# DMX.net
KiCad netlist of a schematic drawn in EAGLE
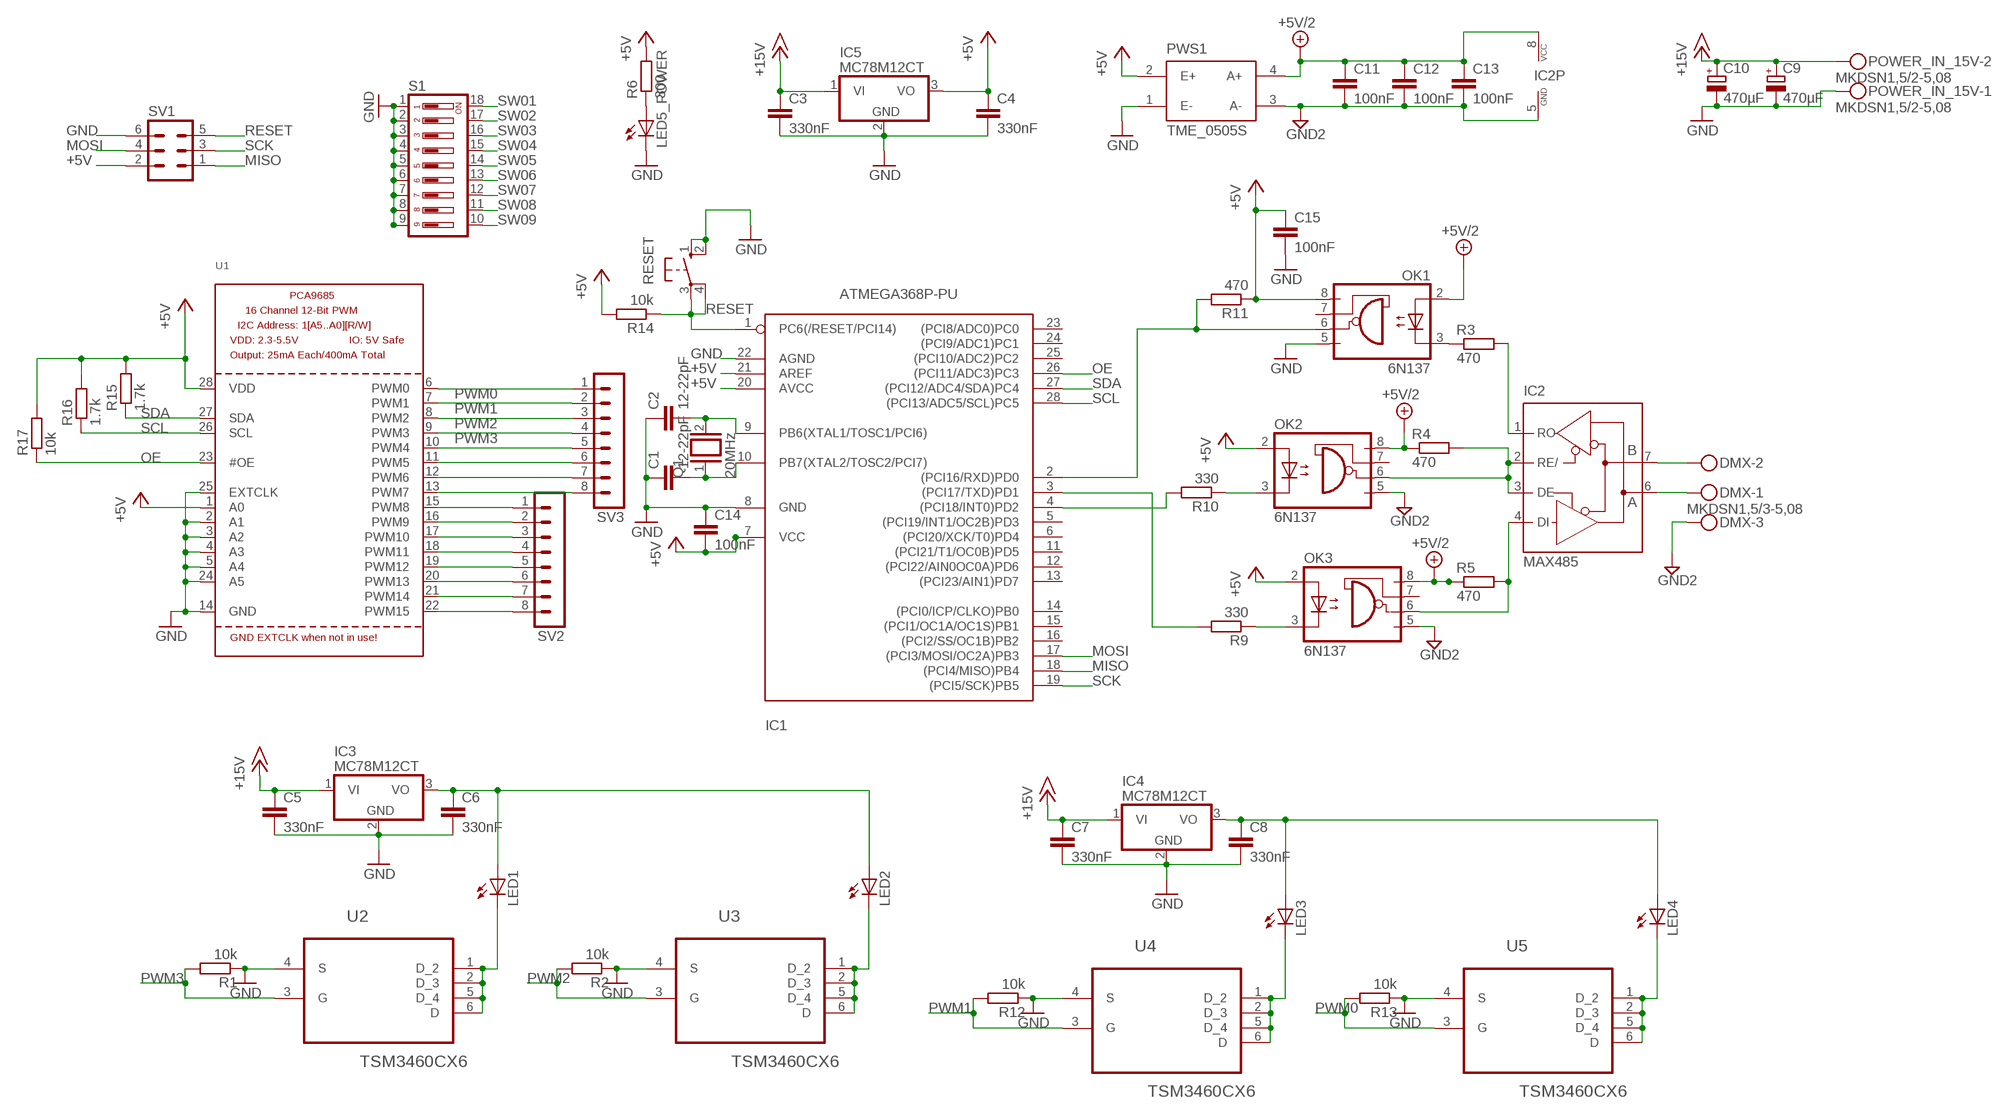
[diagram p0: schematic, sheet 1]

(export (version "E")
  (design (tool "Eeschema 10.0.6"))
  (components
    (comp (ref "C1")
      (value "12-22pF")
      (footprint "eagle-import:C025-025X050")
      (libsource (lib "eagle-import") (part "C-EU025-025X050"))
    )
    (comp (ref "C2")
      (value "12-22pF")
      (footprint "eagle-import:C025-025X050")
      (libsource (lib "eagle-import") (part "C-EU025-025X050"))
    )
    (comp (ref "C3")
      (value "330nF")
      (footprint "eagle-import:C050-025X075")
      (libsource (lib "eagle-import") (part "C-EU050-025X075"))
    )
    (comp (ref "C4")
      (value "330nF")
      (footprint "eagle-import:C050-025X075")
      (libsource (lib "eagle-import") (part "C-EU050-025X075"))
    )
    (comp (ref "C5")
      (value "330nF")
      (footprint "eagle-import:C050-025X075")
      (libsource (lib "eagle-import") (part "C-EU050-025X075"))
    )
    (comp (ref "C6")
      (value "330nF")
      (footprint "eagle-import:C050-025X075")
      (libsource (lib "eagle-import") (part "C-EU050-025X075"))
    )
    (comp (ref "C7")
      (value "330nF")
      (footprint "eagle-import:C050-025X075")
      (libsource (lib "eagle-import") (part "C-EU050-025X075"))
    )
    (comp (ref "C8")
      (value "330nF")
      (footprint "eagle-import:C050-025X075")
      (libsource (lib "eagle-import") (part "C-EU050-025X075"))
    )
    (comp (ref "C9")
      (value "470µF")
      (footprint "eagle-import:E5-10,5")
      (libsource (lib "eagle-import") (part "CPOL-EUE5-10.5"))
    )
    (comp (ref "C10")
      (value "470µF")
      (footprint "eagle-import:E5-10,5")
      (libsource (lib "eagle-import") (part "CPOL-EUE5-10.5"))
    )
    (comp (ref "C11")
      (value "100nF")
      (footprint "eagle-import:C050-025X075")
      (libsource (lib "eagle-import") (part "C-EU050-025X075"))
    )
    (comp (ref "C12")
      (value "100nF")
      (footprint "eagle-import:C050-025X075")
      (libsource (lib "eagle-import") (part "C-EU050-025X075"))
    )
    (comp (ref "C13")
      (value "100nF")
      (footprint "eagle-import:C050-025X075")
      (libsource (lib "eagle-import") (part "C-EU050-025X075"))
    )
    (comp (ref "C14")
      (value "100nF")
      (footprint "eagle-import:C050-025X075")
      (libsource (lib "eagle-import") (part "C-EU050-025X075"))
    )
    (comp (ref "C15")
      (value "100nF")
      (footprint "eagle-import:C050-025X075")
      (libsource (lib "eagle-import") (part "C-EU050-025X075"))
    )
    (comp (ref "DMX")
      (value "MKDSN1,5/3-5,08")
      (footprint "eagle-import:MKDSN1,5_3-5,08")
      (fields (field (name "MPN") "SMKDSN1,5/3-5,08"))
      (libsource (lib "eagle-import") (part "MKDSN1,5/3-5,08"))
    )
    (comp (ref "IC1")
      (value "ATMEGA368P-PU")
      (footprint "eagle-import:DIL28-3")
      (libsource (lib "eagle-import") (part "ATMEGA168P-20"))
    )
    (comp (ref "IC2")
      (value "MAX485")
      (footprint "eagle-import:DIL08")
      (fields (field (name "MPN") "MAX481CPA+") (field (name "MPN_1") "MAX485"))
      (libsource (lib "eagle-import") (part "MAX481CPA"))
    )
    (comp (ref "IC3")
      (value "MC78M12CT")
      (footprint "eagle-import:TO220V")
      (libsource (lib "eagle-import") (part "MC78MT12C"))
    )
    (comp (ref "IC4")
      (value "MC78M12CT")
      (footprint "eagle-import:TO220V")
      (libsource (lib "eagle-import") (part "MC78MT12C"))
    )
    (comp (ref "IC5")
      (value "MC78M12CT")
      (footprint "eagle-import:TO220V")
      (libsource (lib "eagle-import") (part "MC78MT12C"))
    )
    (comp (ref "LED1")
      (value "LED5MM")
      (footprint "eagle-import:LED5MM")
      (libsource (lib "eagle-import") (part "LED5MM"))
    )
    (comp (ref "LED2")
      (value "LED5MM")
      (footprint "eagle-import:LED5MM")
      (libsource (lib "eagle-import") (part "LED5MM"))
    )
    (comp (ref "LED3")
      (value "LED5MM")
      (footprint "eagle-import:LED5MM")
      (libsource (lib "eagle-import") (part "LED5MM"))
    )
    (comp (ref "LED4")
      (value "LED5MM")
      (footprint "eagle-import:LED5MM")
      (libsource (lib "eagle-import") (part "LED5MM"))
    )
    (comp (ref "LED5_POWER")
      (value "LED5MM")
      (footprint "eagle-import:LED5MM")
      (libsource (lib "eagle-import") (part "LED5MM"))
    )
    (comp (ref "OK1")
      (value "6N137")
      (footprint "eagle-import:DIL08")
      (libsource (lib "eagle-import") (part "6N137"))
    )
    (comp (ref "OK2")
      (value "6N137")
      (footprint "eagle-import:DIL08")
      (libsource (lib "eagle-import") (part "6N137"))
    )
    (comp (ref "OK3")
      (value "6N137")
      (footprint "eagle-import:DIL08")
      (libsource (lib "eagle-import") (part "6N137"))
    )
    (comp (ref "POWER_IN_15V")
      (value "MKDSN1,5/2-5,08")
      (footprint "eagle-import:MKDSN1,5_2-5,08")
      (fields (field (name "MPN") "MKDSN 1,5/2-5.08"))
      (libsource (lib "eagle-import") (part "MKDSN1,5/2-5,08"))
    )
    (comp (ref "PWS1")
      (value "TME_0505S")
      (footprint "eagle-import:TMEXXXXS")
      (fields (field (name "MPN") "TME 0505S"))
      (libsource (lib "eagle-import") (part "TME_S0505"))
    )
    (comp (ref "Q1")
      (value "20MHz")
      (footprint "eagle-import:QS")
      (libsource (lib "eagle-import") (part "XTAL/S"))
    )
    (comp (ref "R1")
      (value "10k")
      (footprint "eagle-import:0207_7")
      (libsource (lib "eagle-import") (part "R-EU_0207/7"))
    )
    (comp (ref "R2")
      (value "10k")
      (footprint "eagle-import:0207_7")
      (libsource (lib "eagle-import") (part "R-EU_0207/7"))
    )
    (comp (ref "R3")
      (value "470")
      (footprint "eagle-import:0207_7")
      (libsource (lib "eagle-import") (part "R-EU_0207/7"))
    )
    (comp (ref "R4")
      (value "470")
      (footprint "eagle-import:0207_7")
      (libsource (lib "eagle-import") (part "R-EU_0207/7"))
    )
    (comp (ref "R5")
      (value "470")
      (footprint "eagle-import:0207_7")
      (libsource (lib "eagle-import") (part "R-EU_0207/7"))
    )
    (comp (ref "R6")
      (value "300")
      (footprint "eagle-import:0204_7")
      (libsource (lib "eagle-import") (part "R-EU_0204/7"))
    )
    (comp (ref "R9")
      (value "330")
      (footprint "eagle-import:0207_7")
      (libsource (lib "eagle-import") (part "R-EU_0207/7"))
    )
    (comp (ref "R10")
      (value "330")
      (footprint "eagle-import:0207_7")
      (libsource (lib "eagle-import") (part "R-EU_0207/7"))
    )
    (comp (ref "R11")
      (value "470")
      (footprint "eagle-import:0207_7")
      (libsource (lib "eagle-import") (part "R-EU_0207/7"))
    )
    (comp (ref "R12")
      (value "10k")
      (footprint "eagle-import:0207_7")
      (libsource (lib "eagle-import") (part "R-EU_0207/7"))
    )
    (comp (ref "R13")
      (value "10k")
      (footprint "eagle-import:0207_7")
      (libsource (lib "eagle-import") (part "R-EU_0207/7"))
    )
    (comp (ref "R14")
      (value "10k")
      (footprint "eagle-import:0204_7")
      (libsource (lib "eagle-import") (part "R-EU_0204/7"))
    )
    (comp (ref "R15")
      (value "1.7k")
      (footprint "eagle-import:0204_7")
      (libsource (lib "eagle-import") (part "R-EU_0204/7"))
    )
    (comp (ref "R16")
      (value "1.7k")
      (footprint "eagle-import:0204_7")
      (libsource (lib "eagle-import") (part "R-EU_0204/7"))
    )
    (comp (ref "R17")
      (value "10k")
      (footprint "eagle-import:0204_7")
      (libsource (lib "eagle-import") (part "R-EU_0204/7"))
    )
    (comp (ref "RESET")
      (value "10-XX")
      (footprint "eagle-import:B3F-10XX")
      (fields (field (name "MPN") "B3F-1000"))
      (libsource (lib "eagle-import") (part "10-XX"))
    )
    (comp (ref "S1")
      (value "DP09")
      (footprint "eagle-import:DP-09")
      (fields (field (name "MPN") "MCDP09"))
      (libsource (lib "eagle-import") (part "DP09"))
    )
    (comp (ref "SV1")
      (value "MA03-2")
      (footprint "eagle-import:MA03-2")
      (libsource (lib "eagle-import") (part "MA03-2"))
    )
    (comp (ref "SV2")
      (value "MA08-1")
      (footprint "eagle-import:MA08-1")
      (libsource (lib "eagle-import") (part "MA08-1"))
    )
    (comp (ref "SV3")
      (value "MA08-1")
      (footprint "eagle-import:MA08-1")
      (libsource (lib "eagle-import") (part "MA08-1"))
    )
    (comp (ref "U1")
      (value "PCA9685")
      (footprint "eagle-import:TSSOP28")
      (libsource (lib "eagle-import") (part "PCA9685"))
    )
    (comp (ref "U2")
      (value "TSM3460CX6")
      (footprint "eagle-import:SOT95P280X120-6N")
      (libsource (lib "eagle-import") (part "TSM3460CX6"))
    )
    (comp (ref "U3")
      (value "TSM3460CX6")
      (footprint "eagle-import:SOT95P280X120-6N")
      (libsource (lib "eagle-import") (part "TSM3460CX6"))
    )
    (comp (ref "U4")
      (value "TSM3460CX6")
      (footprint "eagle-import:SOT95P280X120-6N")
      (libsource (lib "eagle-import") (part "TSM3460CX6"))
    )
    (comp (ref "U5")
      (value "TSM3460CX6")
      (footprint "eagle-import:SOT95P280X120-6N")
      (libsource (lib "eagle-import") (part "TSM3460CX6"))
    )
  )
  (nets
    (net (code "1") (name "+5V") (class "Default")
      (node (ref "C14") (pin "2") (pinfunction "2_2") (pintype "passive"))
      (node (ref "C15") (pin "1") (pinfunction "1_1") (pintype "passive"))
      (node (ref "C4") (pin "1") (pinfunction "1_1") (pintype "passive"))
      (node (ref "IC1") (pin "20") (pinfunction "AVCC_20") (pintype "bidirectional"))
      (node (ref "IC1") (pin "21") (pinfunction "AREF_21") (pintype "bidirectional"))
      (node (ref "IC1") (pin "7") (pinfunction "VCC_7") (pintype "bidirectional"))
      (node (ref "IC5") (pin "3") (pinfunction "VO_3") (pintype "passive"))
      (node (ref "OK1") (pin "8") (pinfunction "VCC_8") (pintype "passive"))
      (node (ref "OK2") (pin "2") (pinfunction "A_2") (pintype "passive"))
      (node (ref "OK3") (pin "2") (pinfunction "A_2") (pintype "passive"))
      (node (ref "PWS1") (pin "2") (pinfunction "E+_2") (pintype "input"))
      (node (ref "R11") (pin "1") (pinfunction "1_1") (pintype "passive"))
      (node (ref "R14") (pin "2") (pinfunction "2_2") (pintype "passive"))
      (node (ref "R15") (pin "2") (pinfunction "2_2") (pintype "passive"))
      (node (ref "R16") (pin "2") (pinfunction "2_2") (pintype "passive"))
      (node (ref "R17") (pin "2") (pinfunction "2_2") (pintype "passive"))
      (node (ref "R6") (pin "2") (pinfunction "2_2") (pintype "passive"))
      (node (ref "SV1") (pin "2") (pinfunction "2_2") (pintype "passive"))
      (node (ref "U1") (pin "1") (pinfunction "A0_1") (pintype "bidirectional"))
      (node (ref "U1") (pin "28") (pinfunction "VDD_28") (pintype "power_in"))
    )
    (net (code "2") (name "+5V{slash}2") (class "Default")
      (node (ref "C11") (pin "1") (pinfunction "1_1") (pintype "passive"))
      (node (ref "C12") (pin "1") (pinfunction "1_1") (pintype "passive"))
      (node (ref "C13") (pin "1") (pinfunction "1_1") (pintype "passive"))
      (node (ref "IC2") (pin "8") (pinfunction "VCC_8") (pintype "power_in"))
      (node (ref "OK1") (pin "2") (pinfunction "A_2") (pintype "passive"))
      (node (ref "OK2") (pin "8") (pinfunction "VCC_8") (pintype "passive"))
      (node (ref "OK3") (pin "8") (pinfunction "VCC_8") (pintype "passive"))
      (node (ref "PWS1") (pin "4") (pinfunction "A+_4") (pintype "output"))
      (node (ref "R4") (pin "1") (pinfunction "1_1") (pintype "passive"))
      (node (ref "R5") (pin "1") (pinfunction "1_1") (pintype "passive"))
    )
    (net (code "3") (name "+15V") (class "Default")
      (node (ref "C10") (pin "+") (pinfunction "+_+") (pintype "passive"))
      (node (ref "C3") (pin "1") (pinfunction "1_1") (pintype "passive"))
      (node (ref "C5") (pin "1") (pinfunction "1_1") (pintype "passive"))
      (node (ref "C7") (pin "1") (pinfunction "1_1") (pintype "passive"))
      (node (ref "C9") (pin "+") (pinfunction "+_+") (pintype "passive"))
      (node (ref "IC3") (pin "1") (pinfunction "VI_1") (pintype "input"))
      (node (ref "IC4") (pin "1") (pinfunction "VI_1") (pintype "input"))
      (node (ref "IC5") (pin "1") (pinfunction "VI_1") (pintype "input"))
      (node (ref "POWER_IN_15V") (pin "2") (pinfunction "KL_2") (pintype "passive"))
    )
    (net (code "4") (name "/MISO") (class "Default")
      (node (ref "IC1") (pin "18") (pinfunction "(PCI4/MISO)PB4_18") (pintype "bidirectional"))
      (node (ref "SV1") (pin "1") (pinfunction "1_1") (pintype "passive"))
    )
    (net (code "5") (name "/MOSI") (class "Default")
      (node (ref "IC1") (pin "17") (pinfunction "(PCI3/MOSI/OC2A)PB3_17") (pintype "bidirectional"))
      (node (ref "SV1") (pin "4") (pinfunction "4_4") (pintype "passive"))
    )
    (net (code "6") (name "/OE") (class "Default")
      (node (ref "IC1") (pin "26") (pinfunction "(PCI11/ADC3)PC3_26") (pintype "bidirectional"))
      (node (ref "R17") (pin "1") (pinfunction "1_1") (pintype "passive"))
      (node (ref "U1") (pin "23") (pinfunction "#OE_23") (pintype "input"))
    )
    (net (code "7") (name "/PWM0") (class "Default")
      (node (ref "R13") (pin "2") (pinfunction "2_2") (pintype "passive"))
      (node (ref "SV3") (pin "1") (pinfunction "1_1") (pintype "passive"))
      (node (ref "U1") (pin "6") (pinfunction "PWM0_6") (pintype "output"))
      (node (ref "U5") (pin "3") (pinfunction "G_3") (pintype "passive"))
    )
    (net (code "8") (name "/PWM1") (class "Default")
      (node (ref "R12") (pin "2") (pinfunction "2_2") (pintype "passive"))
      (node (ref "SV3") (pin "2") (pinfunction "2_2") (pintype "passive"))
      (node (ref "U1") (pin "7") (pinfunction "PWM1_7") (pintype "output"))
      (node (ref "U4") (pin "3") (pinfunction "G_3") (pintype "passive"))
    )
    (net (code "9") (name "/PWM2") (class "Default")
      (node (ref "R2") (pin "2") (pinfunction "2_2") (pintype "passive"))
      (node (ref "SV3") (pin "3") (pinfunction "3_3") (pintype "passive"))
      (node (ref "U1") (pin "8") (pinfunction "PWM2_8") (pintype "output"))
      (node (ref "U3") (pin "3") (pinfunction "G_3") (pintype "passive"))
    )
    (net (code "10") (name "/PWM3") (class "Default")
      (node (ref "R1") (pin "2") (pinfunction "2_2") (pintype "passive"))
      (node (ref "SV3") (pin "4") (pinfunction "4_4") (pintype "passive"))
      (node (ref "U1") (pin "9") (pinfunction "PWM3_9") (pintype "output"))
      (node (ref "U2") (pin "3") (pinfunction "G_3") (pintype "passive"))
    )
    (net (code "11") (name "/RESET") (class "Default")
      (node (ref "IC1") (pin "1") (pinfunction "PC6(/RESET/PCI14)_1") (pintype "bidirectional"))
      (node (ref "R14") (pin "1") (pinfunction "1_1") (pintype "passive"))
      (node (ref "RESET") (pin "3") (pinfunction "P_3") (pintype "passive"))
      (node (ref "RESET") (pin "4") (pinfunction "P1_4") (pintype "passive"))
      (node (ref "SV1") (pin "5") (pinfunction "5_5") (pintype "passive"))
    )
    (net (code "12") (name "/SCK") (class "Default")
      (node (ref "IC1") (pin "19") (pinfunction "(PCI5/SCK)PB5_19") (pintype "bidirectional"))
      (node (ref "SV1") (pin "3") (pinfunction "3_3") (pintype "passive"))
    )
    (net (code "13") (name "/SCL") (class "Default")
      (node (ref "IC1") (pin "28") (pinfunction "(PCI13/ADC5/SCL)PC5_28") (pintype "bidirectional"))
      (node (ref "R16") (pin "1") (pinfunction "1_1") (pintype "passive"))
      (node (ref "U1") (pin "26") (pinfunction "SCL_26") (pintype "bidirectional"))
    )
    (net (code "14") (name "/SDA") (class "Default")
      (node (ref "IC1") (pin "27") (pinfunction "(PCI12/ADC4/SDA)PC4_27") (pintype "bidirectional"))
      (node (ref "R15") (pin "1") (pinfunction "1_1") (pintype "passive"))
      (node (ref "U1") (pin "27") (pinfunction "SDA_27") (pintype "bidirectional"))
    )
    (net (code "15") (name "/SW01") (class "Default")
      (node (ref "S1") (pin "18") (pinfunction "18_18") (pintype "passive"))
    )
    (net (code "16") (name "/SW02") (class "Default")
      (node (ref "S1") (pin "17") (pinfunction "17_17") (pintype "passive"))
    )
    (net (code "17") (name "/SW03") (class "Default")
      (node (ref "S1") (pin "16") (pinfunction "16_16") (pintype "passive"))
    )
    (net (code "18") (name "/SW04") (class "Default")
      (node (ref "S1") (pin "15") (pinfunction "15_15") (pintype "passive"))
    )
    (net (code "19") (name "/SW05") (class "Default")
      (node (ref "S1") (pin "14") (pinfunction "14_14") (pintype "passive"))
    )
    (net (code "20") (name "/SW06") (class "Default")
      (node (ref "S1") (pin "13") (pinfunction "13_13") (pintype "passive"))
    )
    (net (code "21") (name "/SW07") (class "Default")
      (node (ref "S1") (pin "12") (pinfunction "12_12") (pintype "passive"))
    )
    (net (code "22") (name "/SW08") (class "Default")
      (node (ref "S1") (pin "11") (pinfunction "11_11") (pintype "passive"))
    )
    (net (code "23") (name "/SW09") (class "Default")
      (node (ref "S1") (pin "10") (pinfunction "10_10") (pintype "passive"))
    )
    (net (code "24") (name "GND") (class "Default")
      (node (ref "C1") (pin "1") (pinfunction "1_1") (pintype "passive"))
      (node (ref "C10") (pin "-") (pinfunction "-_-") (pintype "passive"))
      (node (ref "C14") (pin "1") (pinfunction "1_1") (pintype "passive"))
      (node (ref "C15") (pin "2") (pinfunction "2_2") (pintype "passive"))
      (node (ref "C2") (pin "1") (pinfunction "1_1") (pintype "passive"))
      (node (ref "C3") (pin "2") (pinfunction "2_2") (pintype "passive"))
      (node (ref "C4") (pin "2") (pinfunction "2_2") (pintype "passive"))
      (node (ref "C5") (pin "2") (pinfunction "2_2") (pintype "passive"))
      (node (ref "C6") (pin "2") (pinfunction "2_2") (pintype "passive"))
      (node (ref "C7") (pin "2") (pinfunction "2_2") (pintype "passive"))
      (node (ref "C8") (pin "2") (pinfunction "2_2") (pintype "passive"))
      (node (ref "C9") (pin "-") (pinfunction "-_-") (pintype "passive"))
      (node (ref "IC1") (pin "22") (pinfunction "AGND_22") (pintype "bidirectional"))
      (node (ref "IC1") (pin "8") (pinfunction "GND_8") (pintype "bidirectional"))
      (node (ref "IC3") (pin "2") (pinfunction "GND_2") (pintype "passive"))
      (node (ref "IC4") (pin "2") (pinfunction "GND_2") (pintype "passive"))
      (node (ref "IC5") (pin "2") (pinfunction "GND_2") (pintype "passive"))
      (node (ref "LED5_POWER") (pin "K") (pinfunction "C_K") (pintype "passive"))
      (node (ref "OK1") (pin "5") (pinfunction "GND_5") (pintype "passive"))
      (node (ref "POWER_IN_15V") (pin "1") (pinfunction "KL_1") (pintype "passive"))
      (node (ref "PWS1") (pin "1") (pinfunction "E-_1") (pintype "input"))
      (node (ref "R1") (pin "1") (pinfunction "1_1") (pintype "passive"))
      (node (ref "R12") (pin "1") (pinfunction "1_1") (pintype "passive"))
      (node (ref "R13") (pin "1") (pinfunction "1_1") (pintype "passive"))
      (node (ref "R2") (pin "1") (pinfunction "1_1") (pintype "passive"))
      (node (ref "RESET") (pin "1") (pinfunction "S_1") (pintype "passive"))
      (node (ref "RESET") (pin "2") (pinfunction "S1_2") (pintype "passive"))
      (node (ref "S1") (pin "1") (pinfunction "1_1") (pintype "passive"))
      (node (ref "S1") (pin "2") (pinfunction "2_2") (pintype "passive"))
      (node (ref "S1") (pin "3") (pinfunction "3_3") (pintype "passive"))
      (node (ref "S1") (pin "4") (pinfunction "4_4") (pintype "passive"))
      (node (ref "S1") (pin "5") (pinfunction "5_5") (pintype "passive"))
      (node (ref "S1") (pin "6") (pinfunction "6_6") (pintype "passive"))
      (node (ref "S1") (pin "7") (pinfunction "7_7") (pintype "passive"))
      (node (ref "S1") (pin "8") (pinfunction "8_8") (pintype "passive"))
      (node (ref "S1") (pin "9") (pinfunction "9_9") (pintype "passive"))
      (node (ref "SV1") (pin "6") (pinfunction "6_6") (pintype "passive"))
      (node (ref "U1") (pin "14") (pinfunction "GND_14") (pintype "power_in"))
      (node (ref "U1") (pin "2") (pinfunction "A1_2") (pintype "bidirectional"))
      (node (ref "U1") (pin "24") (pinfunction "A5_24") (pintype "bidirectional"))
      (node (ref "U1") (pin "25") (pinfunction "EXTCLK_25") (pintype "input"))
      (node (ref "U1") (pin "3") (pinfunction "A2_3") (pintype "bidirectional"))
      (node (ref "U1") (pin "4") (pinfunction "A3_4") (pintype "bidirectional"))
      (node (ref "U1") (pin "5") (pinfunction "A4_5") (pintype "bidirectional"))
      (node (ref "U2") (pin "4") (pinfunction "S_4") (pintype "passive"))
      (node (ref "U3") (pin "4") (pinfunction "S_4") (pintype "passive"))
      (node (ref "U4") (pin "4") (pinfunction "S_4") (pintype "passive"))
      (node (ref "U5") (pin "4") (pinfunction "S_4") (pintype "passive"))
    )
    (net (code "25") (name "GND2") (class "Default")
      (node (ref "C11") (pin "2") (pinfunction "2_2") (pintype "passive"))
      (node (ref "C12") (pin "2") (pinfunction "2_2") (pintype "passive"))
      (node (ref "C13") (pin "2") (pinfunction "2_2") (pintype "passive"))
      (node (ref "DMX") (pin "3") (pinfunction "KL_3") (pintype "passive"))
      (node (ref "IC2") (pin "5") (pinfunction "GND_5") (pintype "power_in"))
      (node (ref "OK2") (pin "5") (pinfunction "GND_5") (pintype "passive"))
      (node (ref "OK3") (pin "5") (pinfunction "GND_5") (pintype "passive"))
      (node (ref "PWS1") (pin "3") (pinfunction "A-_3") (pintype "output"))
    )
    (net (code "26") (name "Net-(DMXA-KL)") (class "Default")
      (node (ref "DMX") (pin "1") (pinfunction "KL_1") (pintype "passive"))
      (node (ref "IC2") (pin "6") (pinfunction "A_6") (pintype "passive"))
    )
    (net (code "27") (name "Net-(DMXB-KL)") (class "Default")
      (node (ref "DMX") (pin "2") (pinfunction "KL_2") (pintype "passive"))
      (node (ref "IC2") (pin "7") (pinfunction "B_7") (pintype "passive"))
    )
    (net (code "28") (name "Net-(IC1-(PCI16{slash}RXD)PD0)") (class "Default")
      (node (ref "IC1") (pin "2") (pinfunction "(PCI16/RXD)PD0_2") (pintype "bidirectional"))
      (node (ref "OK1") (pin "6") (pinfunction "VO_6") (pintype "passive"))
      (node (ref "R11") (pin "2") (pinfunction "2_2") (pintype "passive"))
    )
    (net (code "29") (name "Net-(IC1-(PCI17{slash}TXD)PD1)") (class "Default")
      (node (ref "IC1") (pin "3") (pinfunction "(PCI17/TXD)PD1_3") (pintype "bidirectional"))
      (node (ref "R9") (pin "2") (pinfunction "2_2") (pintype "passive"))
    )
    (net (code "30") (name "Net-(IC1-(PCI18{slash}INT0)PD2)") (class "Default")
      (node (ref "IC1") (pin "4") (pinfunction "(PCI18/INT0)PD2_4") (pintype "bidirectional"))
      (node (ref "R10") (pin "2") (pinfunction "2_2") (pintype "passive"))
    )
    (net (code "31") (name "Net-(IC1-PB6(XTAL1{slash}TOSC1{slash}PCI6))") (class "Default")
      (node (ref "C2") (pin "2") (pinfunction "2_2") (pintype "passive"))
      (node (ref "IC1") (pin "9") (pinfunction "PB6(XTAL1/TOSC1/PCI6)_9") (pintype "bidirectional"))
      (node (ref "Q1") (pin "2") (pinfunction "2_2") (pintype "passive"))
    )
    (net (code "32") (name "Net-(IC1-PB7(XTAL2{slash}TOSC2{slash}PCI7))") (class "Default")
      (node (ref "C1") (pin "2") (pinfunction "2_2") (pintype "passive"))
      (node (ref "IC1") (pin "10") (pinfunction "PB7(XTAL2/TOSC2/PCI7)_10") (pintype "bidirectional"))
      (node (ref "Q1") (pin "1") (pinfunction "1_1") (pintype "passive"))
    )
    (net (code "33") (name "Net-(IC2A-DE)") (class "Default")
      (node (ref "IC2") (pin "2") (pinfunction "RE/_2") (pintype "input"))
      (node (ref "IC2") (pin "3") (pinfunction "DE_3") (pintype "input"))
      (node (ref "OK2") (pin "6") (pinfunction "VO_6") (pintype "passive"))
      (node (ref "R4") (pin "2") (pinfunction "2_2") (pintype "passive"))
    )
    (net (code "34") (name "Net-(IC2A-DI)") (class "Default")
      (node (ref "IC2") (pin "4") (pinfunction "DI_4") (pintype "input"))
      (node (ref "OK3") (pin "6") (pinfunction "VO_6") (pintype "passive"))
      (node (ref "R5") (pin "2") (pinfunction "2_2") (pintype "passive"))
    )
    (net (code "35") (name "Net-(IC2A-RO)") (class "Default")
      (node (ref "IC2") (pin "1") (pinfunction "RO_1") (pintype "output"))
      (node (ref "R3") (pin "2") (pinfunction "2_2") (pintype "passive"))
    )
    (net (code "36") (name "Net-(IC3-VO)") (class "Default")
      (node (ref "C6") (pin "1") (pinfunction "1_1") (pintype "passive"))
      (node (ref "IC3") (pin "3") (pinfunction "VO_3") (pintype "passive"))
      (node (ref "LED1") (pin "A") (pinfunction "A_A") (pintype "passive"))
      (node (ref "LED2") (pin "A") (pinfunction "A_A") (pintype "passive"))
    )
    (net (code "37") (name "Net-(IC4-VO)") (class "Default")
      (node (ref "C8") (pin "1") (pinfunction "1_1") (pintype "passive"))
      (node (ref "IC4") (pin "3") (pinfunction "VO_3") (pintype "passive"))
      (node (ref "LED3") (pin "A") (pinfunction "A_A") (pintype "passive"))
      (node (ref "LED4") (pin "A") (pinfunction "A_A") (pintype "passive"))
    )
    (net (code "38") (name "Net-(LED1-C)") (class "Default")
      (node (ref "LED1") (pin "K") (pinfunction "C_K") (pintype "passive"))
      (node (ref "U2") (pin "1") (pinfunction "D_2_1") (pintype "passive"))
      (node (ref "U2") (pin "2") (pinfunction "D_3_2") (pintype "passive"))
      (node (ref "U2") (pin "5") (pinfunction "D_4_5") (pintype "passive"))
      (node (ref "U2") (pin "6") (pinfunction "D_6") (pintype "passive"))
    )
    (net (code "39") (name "Net-(LED2-C)") (class "Default")
      (node (ref "LED2") (pin "K") (pinfunction "C_K") (pintype "passive"))
      (node (ref "U3") (pin "1") (pinfunction "D_2_1") (pintype "passive"))
      (node (ref "U3") (pin "2") (pinfunction "D_3_2") (pintype "passive"))
      (node (ref "U3") (pin "5") (pinfunction "D_4_5") (pintype "passive"))
      (node (ref "U3") (pin "6") (pinfunction "D_6") (pintype "passive"))
    )
    (net (code "40") (name "Net-(LED3-C)") (class "Default")
      (node (ref "LED3") (pin "K") (pinfunction "C_K") (pintype "passive"))
      (node (ref "U4") (pin "1") (pinfunction "D_2_1") (pintype "passive"))
      (node (ref "U4") (pin "2") (pinfunction "D_3_2") (pintype "passive"))
      (node (ref "U4") (pin "5") (pinfunction "D_4_5") (pintype "passive"))
      (node (ref "U4") (pin "6") (pinfunction "D_6") (pintype "passive"))
    )
    (net (code "41") (name "Net-(LED4-C)") (class "Default")
      (node (ref "LED4") (pin "K") (pinfunction "C_K") (pintype "passive"))
      (node (ref "U5") (pin "1") (pinfunction "D_2_1") (pintype "passive"))
      (node (ref "U5") (pin "2") (pinfunction "D_3_2") (pintype "passive"))
      (node (ref "U5") (pin "5") (pinfunction "D_4_5") (pintype "passive"))
      (node (ref "U5") (pin "6") (pinfunction "D_6") (pintype "passive"))
    )
    (net (code "42") (name "Net-(LED5_POWER-PadA)") (class "Default")
      (node (ref "LED5_POWER") (pin "A") (pinfunction "A_A") (pintype "passive"))
      (node (ref "R6") (pin "1") (pinfunction "1_1") (pintype "passive"))
    )
    (net (code "43") (name "Net-(OK1-C)") (class "Default")
      (node (ref "OK1") (pin "3") (pinfunction "C_3") (pintype "passive"))
      (node (ref "R3") (pin "1") (pinfunction "1_1") (pintype "passive"))
    )
    (net (code "44") (name "Net-(OK2-C)") (class "Default")
      (node (ref "OK2") (pin "3") (pinfunction "C_3") (pintype "passive"))
      (node (ref "R10") (pin "1") (pinfunction "1_1") (pintype "passive"))
    )
    (net (code "45") (name "Net-(OK3-C)") (class "Default")
      (node (ref "OK3") (pin "3") (pinfunction "C_3") (pintype "passive"))
      (node (ref "R9") (pin "1") (pinfunction "1_1") (pintype "passive"))
    )
    (net (code "46") (name "Net-(U1-PWM4)") (class "Default")
      (node (ref "SV3") (pin "5") (pinfunction "5_5") (pintype "passive"))
      (node (ref "U1") (pin "10") (pinfunction "PWM4_10") (pintype "output"))
    )
    (net (code "47") (name "Net-(U1-PWM5)") (class "Default")
      (node (ref "SV3") (pin "6") (pinfunction "6_6") (pintype "passive"))
      (node (ref "U1") (pin "11") (pinfunction "PWM5_11") (pintype "output"))
    )
    (net (code "48") (name "Net-(U1-PWM6)") (class "Default")
      (node (ref "SV3") (pin "7") (pinfunction "7_7") (pintype "passive"))
      (node (ref "U1") (pin "12") (pinfunction "PWM6_12") (pintype "output"))
    )
    (net (code "49") (name "Net-(U1-PWM7)") (class "Default")
      (node (ref "SV3") (pin "8") (pinfunction "8_8") (pintype "passive"))
      (node (ref "U1") (pin "13") (pinfunction "PWM7_13") (pintype "output"))
    )
    (net (code "50") (name "Net-(U1-PWM8)") (class "Default")
      (node (ref "SV2") (pin "1") (pinfunction "1_1") (pintype "passive"))
      (node (ref "U1") (pin "15") (pinfunction "PWM8_15") (pintype "output"))
    )
    (net (code "51") (name "Net-(U1-PWM9)") (class "Default")
      (node (ref "SV2") (pin "2") (pinfunction "2_2") (pintype "passive"))
      (node (ref "U1") (pin "16") (pinfunction "PWM9_16") (pintype "output"))
    )
    (net (code "52") (name "Net-(U1-PWM10)") (class "Default")
      (node (ref "SV2") (pin "3") (pinfunction "3_3") (pintype "passive"))
      (node (ref "U1") (pin "17") (pinfunction "PWM10_17") (pintype "output"))
    )
    (net (code "53") (name "Net-(U1-PWM11)") (class "Default")
      (node (ref "SV2") (pin "4") (pinfunction "4_4") (pintype "passive"))
      (node (ref "U1") (pin "18") (pinfunction "PWM11_18") (pintype "output"))
    )
    (net (code "54") (name "Net-(U1-PWM12)") (class "Default")
      (node (ref "SV2") (pin "5") (pinfunction "5_5") (pintype "passive"))
      (node (ref "U1") (pin "19") (pinfunction "PWM12_19") (pintype "output"))
    )
    (net (code "55") (name "Net-(U1-PWM13)") (class "Default")
      (node (ref "SV2") (pin "6") (pinfunction "6_6") (pintype "passive"))
      (node (ref "U1") (pin "20") (pinfunction "PWM13_20") (pintype "output"))
    )
    (net (code "56") (name "Net-(U1-PWM14)") (class "Default")
      (node (ref "SV2") (pin "7") (pinfunction "7_7") (pintype "passive"))
      (node (ref "U1") (pin "21") (pinfunction "PWM14_21") (pintype "output"))
    )
    (net (code "57") (name "Net-(U1-PWM15)") (class "Default")
      (node (ref "SV2") (pin "8") (pinfunction "8_8") (pintype "passive"))
      (node (ref "U1") (pin "22") (pinfunction "PWM15_22") (pintype "output"))
    )
    (net (code "58") (name "unconnected-(IC1-(PCI0{slash}ICP{slash}CLKO)PB0-Pad14)") (class "Default")
      (node (ref "IC1") (pin "14") (pinfunction "(PCI0/ICP/CLKO)PB0_14") (pintype "bidirectional"))
    )
    (net (code "59") (name "unconnected-(IC1-(PCI1{slash}OC1A{slash}OC1S)PB1-Pad15)") (class "Default")
      (node (ref "IC1") (pin "15") (pinfunction "(PCI1/OC1A/OC1S)PB1_15") (pintype "bidirectional"))
    )
    (net (code "60") (name "unconnected-(IC1-(PCI2{slash}SS{slash}OC1B)PB2-Pad16)") (class "Default")
      (node (ref "IC1") (pin "16") (pinfunction "(PCI2/SS/OC1B)PB2_16") (pintype "bidirectional"))
    )
    (net (code "61") (name "unconnected-(IC1-(PCI8{slash}ADC0)PC0-Pad23)") (class "Default")
      (node (ref "IC1") (pin "23") (pinfunction "(PCI8/ADC0)PC0_23") (pintype "bidirectional"))
    )
    (net (code "62") (name "unconnected-(IC1-(PCI9{slash}ADC1)PC1-Pad24)") (class "Default")
      (node (ref "IC1") (pin "24") (pinfunction "(PCI9/ADC1)PC1_24") (pintype "bidirectional"))
    )
    (net (code "63") (name "unconnected-(IC1-(PCI10{slash}ADC2)PC2-Pad25)") (class "Default")
      (node (ref "IC1") (pin "25") (pinfunction "(PCI10/ADC2)PC2_25") (pintype "bidirectional"))
    )
    (net (code "64") (name "unconnected-(IC1-(PCI19{slash}INT1{slash}OC2B)PD3-Pad5)") (class "Default")
      (node (ref "IC1") (pin "5") (pinfunction "(PCI19/INT1/OC2B)PD3_5") (pintype "bidirectional"))
    )
    (net (code "65") (name "unconnected-(IC1-(PCI20{slash}XCK{slash}T0)PD4-Pad6)") (class "Default")
      (node (ref "IC1") (pin "6") (pinfunction "(PCI20/XCK/T0)PD4_6") (pintype "bidirectional"))
    )
    (net (code "66") (name "unconnected-(IC1-(PCI21{slash}T1{slash}OC0B)PD5-Pad11)") (class "Default")
      (node (ref "IC1") (pin "11") (pinfunction "(PCI21/T1/OC0B)PD5_11") (pintype "bidirectional"))
    )
    (net (code "67") (name "unconnected-(IC1-(PCI22{slash}AIN0OC0A)PD6-Pad12)") (class "Default")
      (node (ref "IC1") (pin "12") (pinfunction "(PCI22/AIN0OC0A)PD6_12") (pintype "bidirectional"))
    )
    (net (code "68") (name "unconnected-(IC1-(PCI23{slash}AIN1)PD7-Pad13)") (class "Default")
      (node (ref "IC1") (pin "13") (pinfunction "(PCI23/AIN1)PD7_13") (pintype "bidirectional"))
    )
    (net (code "69") (name "unconnected-(OK1-VE-Pad7)") (class "Default")
      (node (ref "OK1") (pin "7") (pinfunction "VE_7") (pintype "passive"))
    )
    (net (code "70") (name "unconnected-(OK2-VE-Pad7)") (class "Default")
      (node (ref "OK2") (pin "7") (pinfunction "VE_7") (pintype "passive"))
    )
    (net (code "71") (name "unconnected-(OK3-VE-Pad7)") (class "Default")
      (node (ref "OK3") (pin "7") (pinfunction "VE_7") (pintype "passive"))
    )
  )
)
